# AttinyNodeNRF24.net
KiCad netlist of a schematic drawn in Altium Designer
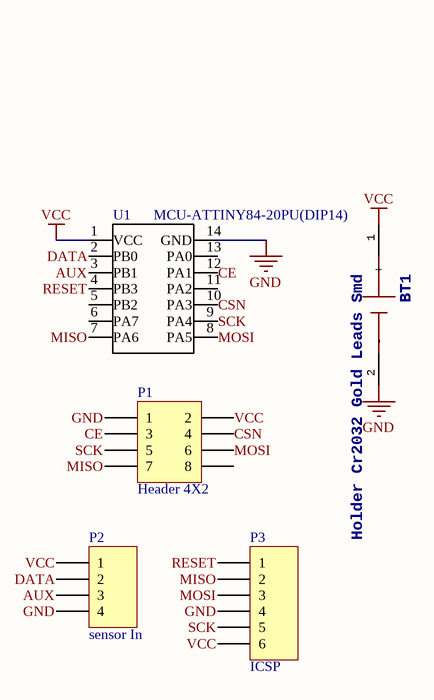
[diagram p0: AttinyNodeNRF24.SchDoc]

(export (version "E")
  (design (tool "Eeschema 10.0.6"))
  (components
    (comp (ref "BT1")
      (value "Holder Cr2032 Gold Leads Smd")
      (footprint "CR2032 Holder _ \"White\"")
      (fields (field (name "MF") "MPD") (field (name "MP") "BU2032SM-BT-GTR"))
      (libsource (lib "Battery Holders") (part "BU2032SM-BT-GTR"))
    )
    (comp (ref "P1")
      (value "Header 4X2")
      (footprint "HDR2X4")
      (description "Header, 4-Pin, Dual row")
      (fields (field (name "PUBLISHER") "Altium Limited"))
      (libsource (lib "Miscellaneous Connectors") (part "Header 4X2"))
    )
    (comp (ref "P2")
      (value "sensor In")
      (footprint "HDR1X4")
      (description "Header, 4-Pin")
      (fields (field (name "PUBLISHER") "Altium Limited"))
      (libsource (lib "Miscellaneous Connectors") (part "Header 4"))
    )
    (comp (ref "P3")
      (value "ICSP")
      (footprint "HDR1X6")
      (description "Header, 6-Pin")
      (fields (field (name "PUBLISHER") "Altium Limited"))
      (libsource (lib "Miscellaneous Connectors") (part "Header 6"))
    )
    (comp (ref "U1")
      (value "MCU-ATTINY84-20PU(DIP14)")
      (footprint "*DIP14-2.54-17.24X6.35MM")
      (description "MCU 8-Bit ATtiny AVR RISC 8KB Flash 3.3V/5V 14-Pin PDIP")
      (fields (field (name "MF") "Microchip") (field (name "MP") "ATTINY84-20PU"))
      (libsource (lib "MCU-ATTINY84-20PU_DIP14_") (part "MCU-ATTINY84-20PU(DIP14)"))
    )
  )
  (nets
    (net (code "1") (name "/AUX") (class "Default")
      (node (ref "P2") (pin "3") (pinfunction "3_3") (pintype "passive"))
      (node (ref "U1") (pin "3") (pinfunction "PB1_3") (pintype "bidirectional"))
    )
    (net (code "2") (name "/CE") (class "Default")
      (node (ref "P1") (pin "3") (pinfunction "3_3") (pintype "passive"))
      (node (ref "U1") (pin "12") (pinfunction "PA1_12") (pintype "bidirectional"))
    )
    (net (code "3") (name "/CSN") (class "Default")
      (node (ref "P1") (pin "4") (pinfunction "4_4") (pintype "passive"))
      (node (ref "U1") (pin "10") (pinfunction "PA3_10") (pintype "bidirectional"))
    )
    (net (code "4") (name "/DATA") (class "Default")
      (node (ref "P2") (pin "2") (pinfunction "2_2") (pintype "passive"))
      (node (ref "U1") (pin "2") (pinfunction "PB0_2") (pintype "bidirectional"))
    )
    (net (code "5") (name "/MISO") (class "Default")
      (node (ref "P1") (pin "7") (pinfunction "7_7") (pintype "passive"))
      (node (ref "P3") (pin "2") (pinfunction "2_2") (pintype "passive"))
      (node (ref "U1") (pin "7") (pinfunction "PA6_7") (pintype "bidirectional"))
    )
    (net (code "6") (name "/MOSI") (class "Default")
      (node (ref "P1") (pin "6") (pinfunction "6_6") (pintype "passive"))
      (node (ref "P3") (pin "3") (pinfunction "3_3") (pintype "passive"))
      (node (ref "U1") (pin "8") (pinfunction "PA5_8") (pintype "bidirectional"))
    )
    (net (code "7") (name "/RESET") (class "Default")
      (node (ref "P3") (pin "1") (pinfunction "1_1") (pintype "passive"))
      (node (ref "U1") (pin "4") (pinfunction "PB3_4") (pintype "bidirectional"))
    )
    (net (code "8") (name "/SCK") (class "Default")
      (node (ref "P1") (pin "5") (pinfunction "5_5") (pintype "passive"))
      (node (ref "P3") (pin "5") (pinfunction "5_5") (pintype "passive"))
      (node (ref "U1") (pin "9") (pinfunction "PA4_9") (pintype "bidirectional"))
    )
    (net (code "9") (name "GND") (class "Default")
      (node (ref "BT1") (pin "2") (pinfunction "-_2") (pintype "passive"))
      (node (ref "P1") (pin "1") (pinfunction "1_1") (pintype "passive"))
      (node (ref "P2") (pin "4") (pinfunction "4_4") (pintype "passive"))
      (node (ref "P3") (pin "4") (pinfunction "4_4") (pintype "passive"))
      (node (ref "U1") (pin "14") (pinfunction "GND_14") (pintype "bidirectional"))
    )
    (net (code "10") (name "VCC") (class "Default")
      (node (ref "BT1") (pin "1") (pinfunction "+_1") (pintype "passive"))
      (node (ref "P1") (pin "2") (pinfunction "2_2") (pintype "passive"))
      (node (ref "P2") (pin "1") (pinfunction "1_1") (pintype "passive"))
      (node (ref "P3") (pin "6") (pinfunction "6_6") (pintype "passive"))
      (node (ref "U1") (pin "1") (pinfunction "VCC_1") (pintype "bidirectional"))
    )
    (net (code "11") (name "unconnected-(P1-Pad8)") (class "Default")
      (node (ref "P1") (pin "8") (pinfunction "8_8") (pintype "passive"))
    )
    (net (code "12") (name "unconnected-(U1-PA0-Pad13)") (class "Default")
      (node (ref "U1") (pin "13") (pinfunction "PA0_13") (pintype "bidirectional"))
    )
    (net (code "13") (name "unconnected-(U1-PA2-Pad11)") (class "Default")
      (node (ref "U1") (pin "11") (pinfunction "PA2_11") (pintype "bidirectional"))
    )
    (net (code "14") (name "unconnected-(U1-PA7-Pad6)") (class "Default")
      (node (ref "U1") (pin "6") (pinfunction "PA7_6") (pintype "bidirectional"))
    )
    (net (code "15") (name "unconnected-(U1-PB2-Pad5)") (class "Default")
      (node (ref "U1") (pin "5") (pinfunction "PB2_5") (pintype "bidirectional"))
    )
  )
)
